# 7h_-_Software_Communication.net
KiCad netlist of a schematic drawn in Altium Designer
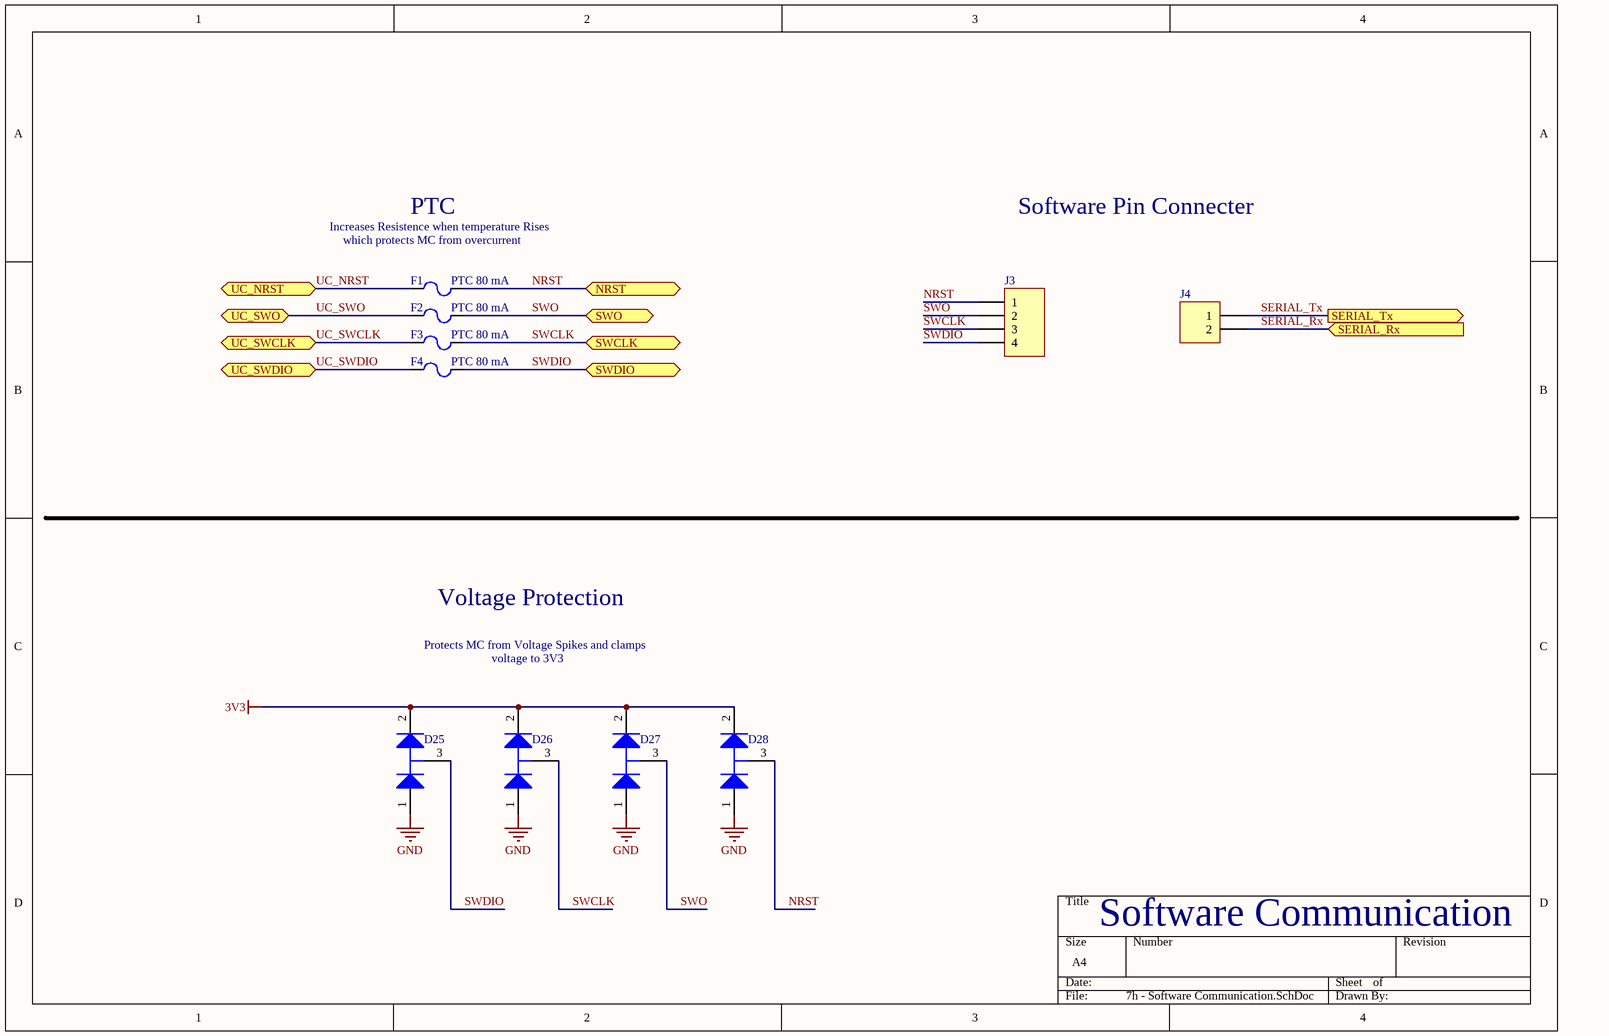
[diagram p0: 7h - Software Communication.SchDoc]

(export (version "E")
  (design (tool "Eeschema 10.0.6"))
  (components
    (comp (ref "D25")
      (value "SZNUP1301ML3T1G")
      (footprint "ONSC-SOT-23-3-318-08_V")
      (fields (field (name "MANUFACTURER") "On Semiconductor"))
      (libsource (lib "Altium Content Vault") (part "ONSC-NUP1301-SOT-23-3-318-08"))
    )
    (comp (ref "D26")
      (value "SZNUP1301ML3T1G")
      (footprint "ONSC-SOT-23-3-318-08_V")
      (fields (field (name "MANUFACTURER") "On Semiconductor"))
      (libsource (lib "Altium Content Vault") (part "ONSC-NUP1301-SOT-23-3-318-08"))
    )
    (comp (ref "D27")
      (value "SZNUP1301ML3T1G")
      (footprint "ONSC-SOT-23-3-318-08_V")
      (fields (field (name "MANUFACTURER") "On Semiconductor"))
      (libsource (lib "Altium Content Vault") (part "ONSC-NUP1301-SOT-23-3-318-08"))
    )
    (comp (ref "D28")
      (value "SZNUP1301ML3T1G")
      (footprint "ONSC-SOT-23-3-318-08_V")
      (fields (field (name "MANUFACTURER") "On Semiconductor"))
      (libsource (lib "Altium Content Vault") (part "ONSC-NUP1301-SOT-23-3-318-08"))
    )
    (comp (ref "F1")
      (value "PTC 80 mA")
      (footprint "FUSC1608X100N")
      (description "0ZCM0008FF2G")
      (libsource (lib "VCU Library") (part "PTC fuse 80mA 0ZCM0008FF2G"))
    )
    (comp (ref "F2")
      (value "PTC 80 mA")
      (footprint "FUSC1608X100N")
      (description "0ZCM0008FF2G")
      (libsource (lib "VCU Library") (part "PTC fuse 80mA 0ZCM0008FF2G"))
    )
    (comp (ref "F3")
      (value "PTC 80 mA")
      (footprint "FUSC1608X100N")
      (description "0ZCM0008FF2G")
      (libsource (lib "VCU Library") (part "PTC fuse 80mA 0ZCM0008FF2G"))
    )
    (comp (ref "F4")
      (value "PTC 80 mA")
      (footprint "FUSC1608X100N")
      (description "0ZCM0008FF2G")
      (libsource (lib "VCU Library") (part "PTC fuse 80mA 0ZCM0008FF2G"))
    )
    (comp (ref "J3")
      (value "Header 4")
      (footprint "HDR1X4")
      (description "Header, 4-Pin")
      (fields (field (name "PUBLISHER") "Altium Limited"))
      (libsource (lib "Miscellaneous Connectors") (part "Header 4"))
    )
    (comp (ref "J4")
      (value "~")
      (footprint "HDR1X2")
      (description "Header, 2-Pin")
      (fields (field (name "PUBLISHER") "Altium Limited"))
      (libsource (lib "Miscellaneous Connectors") (part "Header 2"))
    )
  )
  (nets
    (net (code "1") (name "/NRST") (class "Default")
      (node (ref "D28") (pin "3") (pinfunction "K/A_3") (pintype "passive"))
      (node (ref "F1") (pin "2") (pinfunction "2_2") (pintype "passive"))
      (node (ref "J3") (pin "1") (pinfunction "1_1") (pintype "passive"))
    )
    (net (code "2") (name "/SERIAL_Rx") (class "Default")
      (node (ref "J4") (pin "2") (pinfunction "2_2") (pintype "passive"))
    )
    (net (code "3") (name "/SERIAL_Tx") (class "Default")
      (node (ref "J4") (pin "1") (pinfunction "1_1") (pintype "passive"))
    )
    (net (code "4") (name "/SWCLK") (class "Default")
      (node (ref "D26") (pin "3") (pinfunction "K/A_3") (pintype "passive"))
      (node (ref "F3") (pin "2") (pinfunction "2_2") (pintype "passive"))
      (node (ref "J3") (pin "3") (pinfunction "3_3") (pintype "passive"))
    )
    (net (code "5") (name "/SWDIO") (class "Default")
      (node (ref "D25") (pin "3") (pinfunction "K/A_3") (pintype "passive"))
      (node (ref "F4") (pin "2") (pinfunction "2_2") (pintype "passive"))
      (node (ref "J3") (pin "4") (pinfunction "4_4") (pintype "passive"))
    )
    (net (code "6") (name "/SWO") (class "Default")
      (node (ref "D27") (pin "3") (pinfunction "K/A_3") (pintype "passive"))
      (node (ref "F2") (pin "2") (pinfunction "2_2") (pintype "passive"))
      (node (ref "J3") (pin "2") (pinfunction "2_2") (pintype "passive"))
    )
    (net (code "7") (name "/UC_NRST") (class "Default")
      (node (ref "F1") (pin "1") (pinfunction "1_1") (pintype "passive"))
    )
    (net (code "8") (name "/UC_SWCLK") (class "Default")
      (node (ref "F3") (pin "1") (pinfunction "1_1") (pintype "passive"))
    )
    (net (code "9") (name "/UC_SWDIO") (class "Default")
      (node (ref "F4") (pin "1") (pinfunction "1_1") (pintype "passive"))
    )
    (net (code "10") (name "/UC_SWO") (class "Default")
      (node (ref "F2") (pin "1") (pinfunction "1_1") (pintype "passive"))
    )
    (net (code "11") (name "3V3") (class "Default")
      (node (ref "D25") (pin "2") (pinfunction "K_2") (pintype "passive"))
      (node (ref "D26") (pin "2") (pinfunction "K_2") (pintype "passive"))
      (node (ref "D27") (pin "2") (pinfunction "K_2") (pintype "passive"))
      (node (ref "D28") (pin "2") (pinfunction "K_2") (pintype "passive"))
    )
    (net (code "12") (name "GND") (class "Default")
      (node (ref "D25") (pin "1") (pinfunction "A_1") (pintype "passive"))
      (node (ref "D26") (pin "1") (pinfunction "A_1") (pintype "passive"))
      (node (ref "D27") (pin "1") (pinfunction "A_1") (pintype "passive"))
      (node (ref "D28") (pin "1") (pinfunction "A_1") (pintype "passive"))
    )
  )
)
